# 07-USB-Prog.net
KiCad netlist of a schematic drawn in Altium Designer
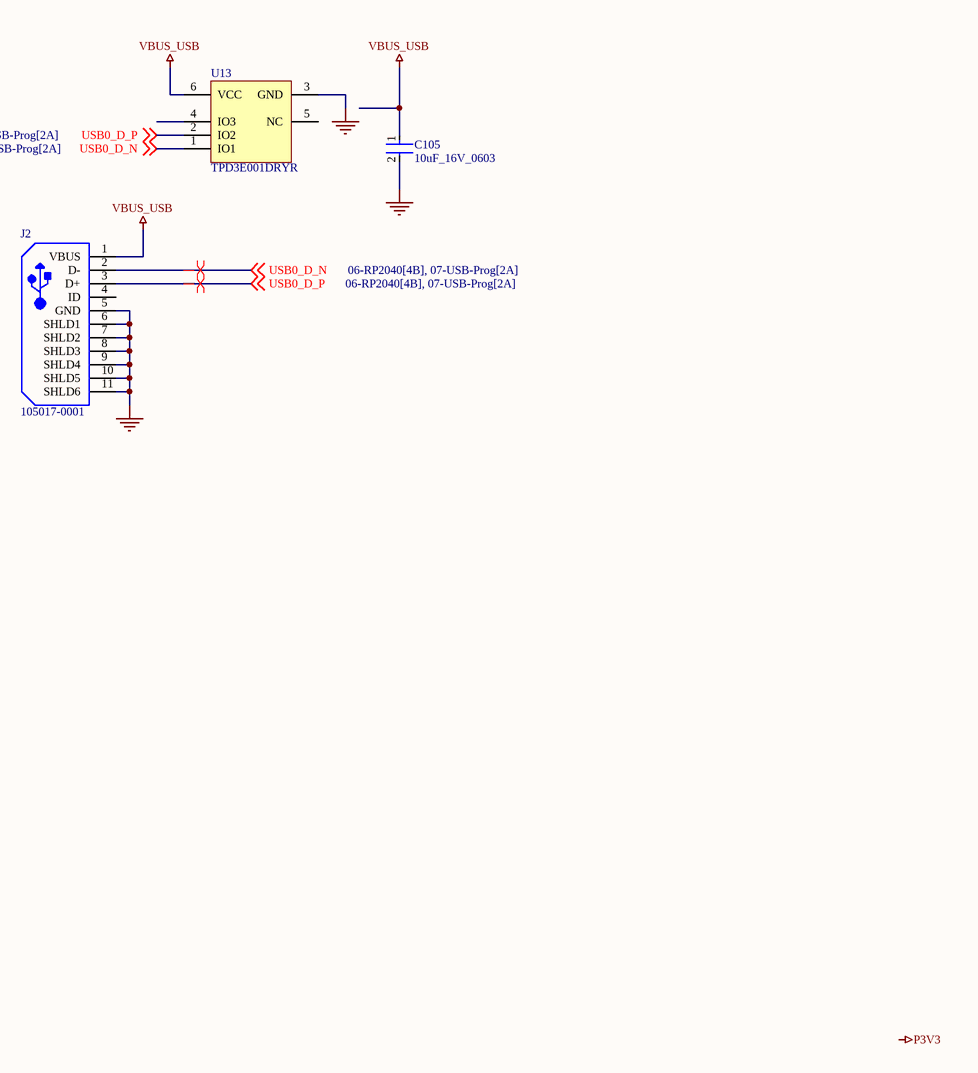
[diagram p0: 07-USB-Prog.SchDoc]

(export (version "E")
  (design (tool "Eeschema 10.0.6"))
  (components
    (comp (ref "C105")
      (value "10uF_16V_0603")
      (footprint "FP-0603-L_1_6_0_2-W_0_8_0-MFG")
      (description "Multilayer Ceramic Capacitor 10uF 16V X5R 20% SMD 0603 T/R")
      (fields (field (name "TOLERANCE") "20%"))
      (libsource (lib "Altium Content Vault") (part "b4654b650e69147ec39a6b967a45e02"))
    )
    (comp (ref "J2")
      (value "105017-0001")
      (footprint "USB-MICRO-B_V")
      (fields (field (name "MANUFACTURER") "Molex"))
      (libsource (lib "Altium Content Vault") (part "USB-5-6SHLD"))
    )
    (comp (ref "U13")
      (value "TPD3E001DRYR")
      (footprint "DRY0006A")
      (fields (field (name "MANUFACTURER") "Texas Instruments"))
      (libsource (lib "Altium Content Vault") (part "TI-TPD3E001-SON_DRY-6"))
    )
  )
  (nets
    (net (code "1") (name "GND") (class "Default")
      (node (ref "C105") (pin "2") (pinfunction "2_2") (pintype "passive"))
      (node (ref "J2") (pin "10") (pinfunction "SHLD5_10") (pintype "passive"))
      (node (ref "J2") (pin "11") (pinfunction "SHLD6_11") (pintype "passive"))
      (node (ref "J2") (pin "5") (pinfunction "GND_5") (pintype "passive"))
      (node (ref "J2") (pin "6") (pinfunction "SHLD1_6") (pintype "passive"))
      (node (ref "J2") (pin "7") (pinfunction "SHLD2_7") (pintype "passive"))
      (node (ref "J2") (pin "8") (pinfunction "SHLD3_8") (pintype "passive"))
      (node (ref "J2") (pin "9") (pinfunction "SHLD4_9") (pintype "passive"))
      (node (ref "U13") (pin "3") (pinfunction "GND_3") (pintype "power_in"))
    )
    (net (code "3") (name "USB0_D_N") (class "Default")
      (node (ref "J2") (pin "2") (pinfunction "D-_2") (pintype "passive"))
      (node (ref "U13") (pin "1") (pinfunction "IO1_1") (pintype "passive"))
    )
    (net (code "4") (name "USB0_D_P") (class "Default")
      (node (ref "J2") (pin "3") (pinfunction "D+_3") (pintype "passive"))
      (node (ref "U13") (pin "2") (pinfunction "IO2_2") (pintype "passive"))
    )
    (net (code "5") (name "VBUS_USB") (class "Default")
      (node (ref "C105") (pin "1") (pinfunction "1_1") (pintype "passive"))
      (node (ref "J2") (pin "1") (pinfunction "VBUS_1") (pintype "passive"))
      (node (ref "U13") (pin "6") (pinfunction "VCC_6") (pintype "power_in"))
    )
    (net (code "6") (name "unconnected-(J2-ID-Pad4)") (class "Default")
      (node (ref "J2") (pin "4") (pinfunction "ID_4") (pintype "passive"))
    )
    (net (code "7") (name "unconnected-(U13-IO3-Pad4)") (class "Default")
      (node (ref "U13") (pin "4") (pinfunction "IO3_4") (pintype "passive"))
    )
    (net (code "8") (name "unconnected-(U13-NC-Pad5)") (class "Default")
      (node (ref "U13") (pin "5") (pinfunction "NC_5") (pintype "passive"))
    )
  )
)
